# Z_-.net
KiCad netlist of a schematic drawn in EasyEDA Pro
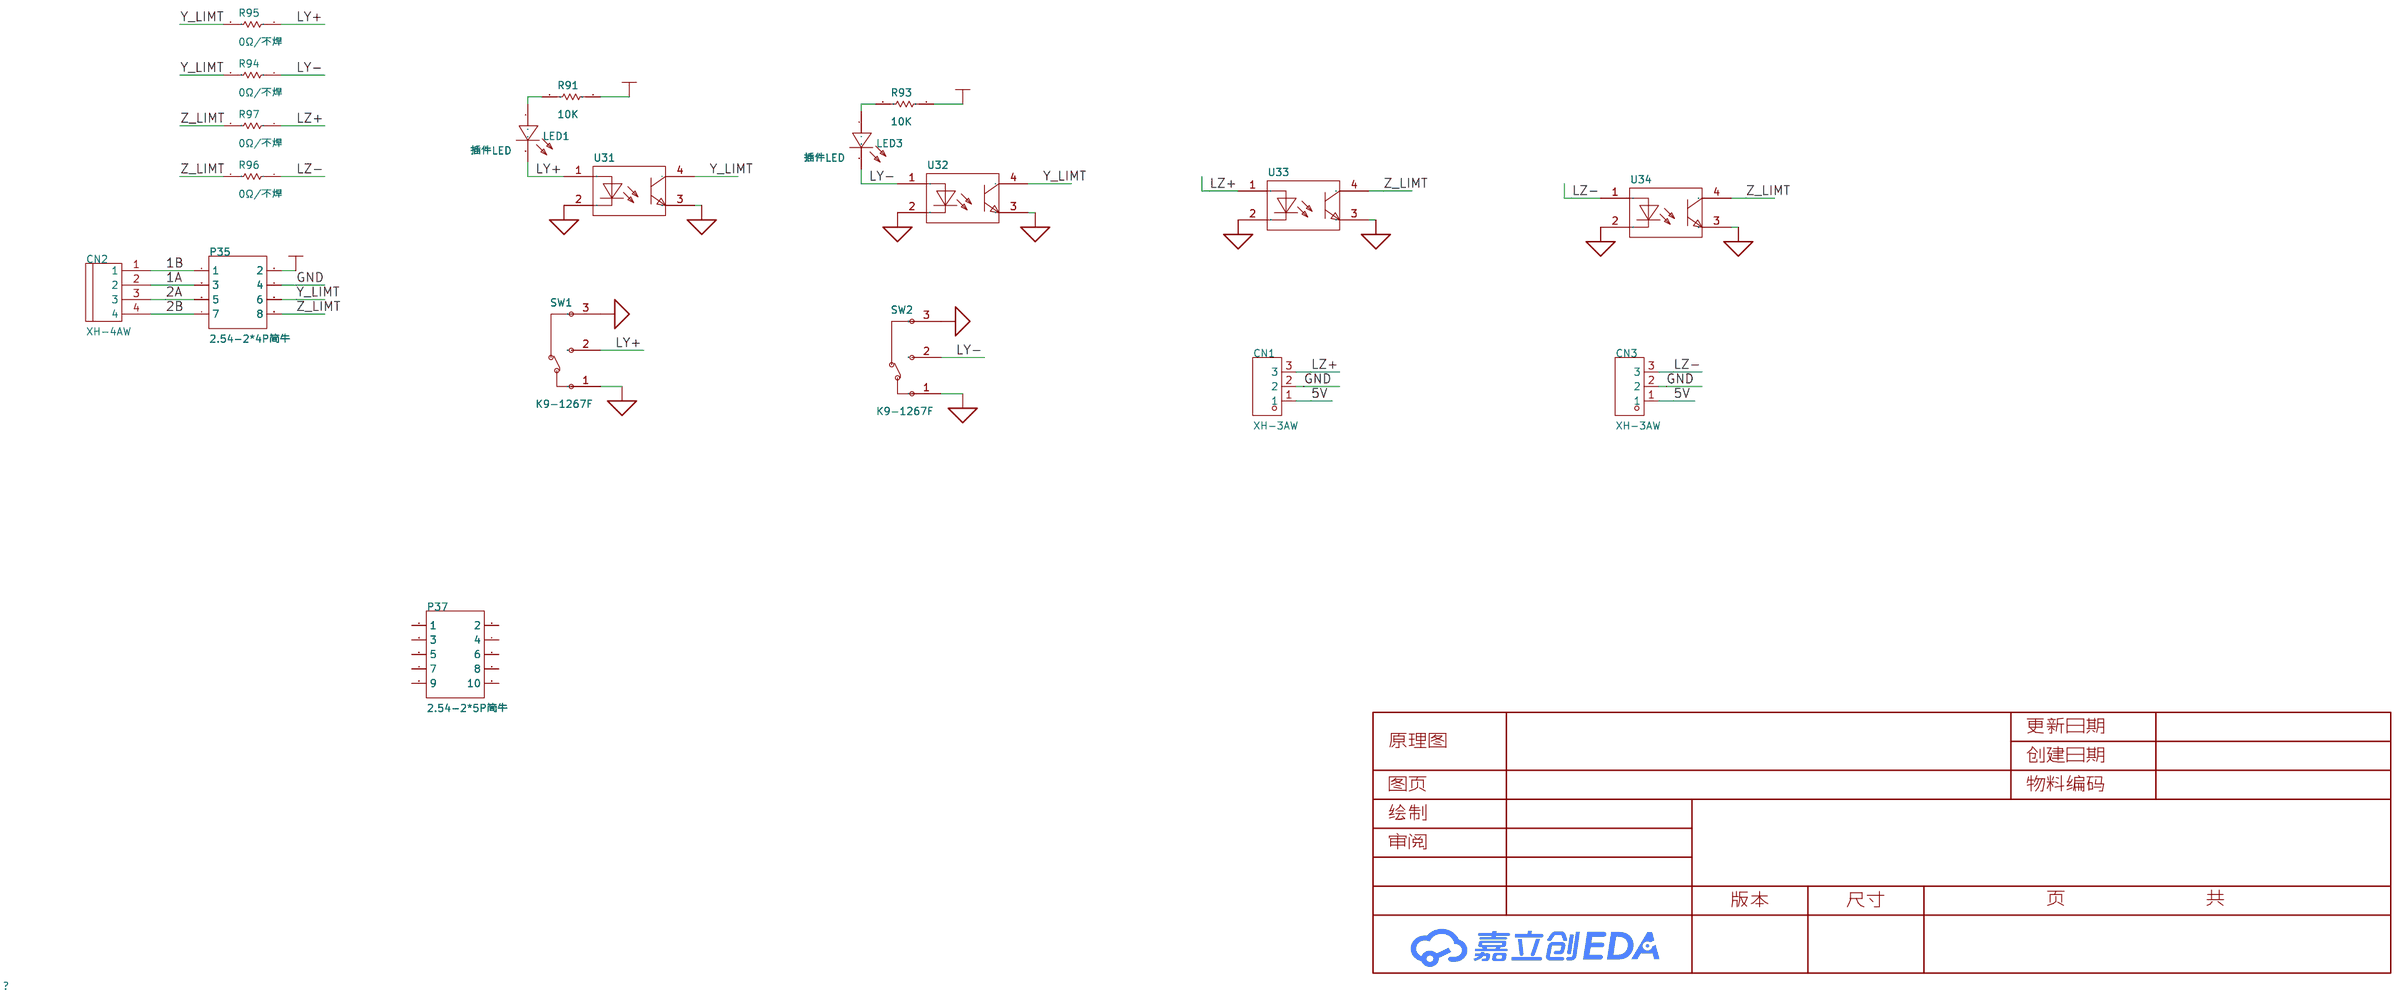
[diagram p0: 主控MCU]
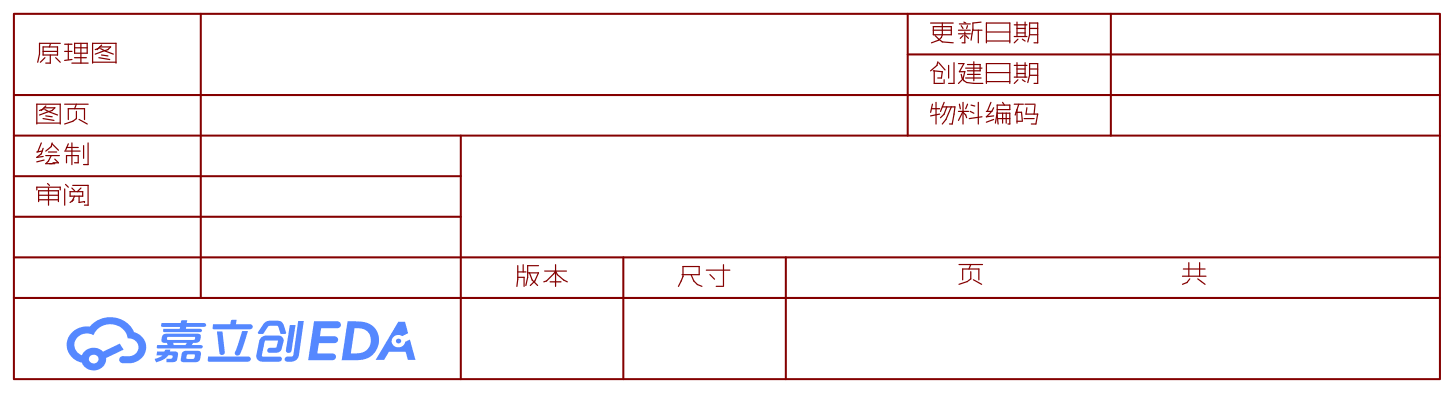
[diagram p1: 电源及控制]

(export (version "E")
  (design (tool "Eeschema 10.0.6"))
  (components
    (comp (ref "CN1")
      (value "XH-3AW")
      (footprint "easyedapro:CONN-TH_3P-P2.50_XH-3A")
      (description "参考系列:XH;间距:2.5mm;插针结构:1x3P;排数:1;每排PIN数:3;行距:-;安装方式:-;触头材质:-;")
      (fields (field (name "Manufacturer") "BOOMELE(博穆精密)"))
      (libsource (lib "easyedapro") (part "XH-3AW_C18428"))
    )
    (comp (ref "CN2")
      (value "XH-4AW")
      (footprint "easyedapro:CONN-TH_XH2.54-4AW")
      (description "参考系列:XH;间距:2.5mm;插针结构:1x4P;排数:1;每排PIN数:4;行距:-;安装方式:-;触头材质:磷青铜;")
      (fields (field (name "Manufacturer") "BOOMELE(博穆精密)"))
      (libsource (lib "easyedapro") (part "XH2.54-4AW"))
    )
    (comp (ref "CN3")
      (value "XH-3AW")
      (footprint "easyedapro:CONN-TH_3P-P2.50_XH-3A")
      (description "参考系列:XH;间距:2.5mm;插针结构:1x3P;排数:1;每排PIN数:3;行距:-;安装方式:-;触头材质:-;")
      (fields (field (name "Manufacturer") "BOOMELE(博穆精密)"))
      (libsource (lib "easyedapro") (part "XH-3AW_C18428"))
    )
    (comp (ref "LED1")
      (value "插件LED")
      (footprint "easyedapro:LED-TH_BD3.8-P2.54-FD")
      (description "发光颜色:红灯;")
      (fields (field (name "Manufacturer") "EVERLIGHT(台湾亿光)"))
      (libsource (lib "easyedapro") (part "204-10SURC/S530-A3-L"))
    )
    (comp (ref "LED3")
      (value "插件LED")
      (footprint "easyedapro:LED-TH_BD3.8-P2.54-FD")
      (description "发光颜色:红灯;")
      (fields (field (name "Manufacturer") "EVERLIGHT(台湾亿光)"))
      (libsource (lib "easyedapro") (part "204-10SURC/S530-A3-L"))
    )
    (comp (ref "P35")
      (value "2.54-2*4P简牛")
      (footprint "easyedapro:IDC-TH_8P-P2.54-V-R2-C4-S2.54")
      (description "连接器类型:简牛座;间距:2.54mm;每排PIN数:4;排数:2;行距:2.54mm;封装形式:直插;触头材质:-;触头镀层:-;")
      (fields (field (name "Manufacturer") "BOOMELE(博穆精密)"))
      (libsource (lib "easyedapro") (part "HDR-IDC-2.54-2X4P"))
    )
    (comp (ref "P37")
      (value "2.54-2*5P简牛")
      (footprint "easyedapro:IDC-TH_10P-P2.54_C5665")
      (description "连接器类型:简牛座;间距:2.54mm;每排PIN数:5;排数:2;行距:2.54mm;封装形式:直插;触头材质:-;触头镀层:-;")
      (fields (field (name "Manufacturer") "BOOMELE(博穆精密)"))
      (libsource (lib "easyedapro") (part "HDR-IDC-2.54-2X5P"))
    )
    (comp (ref "R91")
      (value "10K")
      (footprint "easyedapro:0603R")
      (description "Resistor")
      (libsource (lib "easyedapro") (part "RES"))
    )
    (comp (ref "R93")
      (value "10K")
      (footprint "easyedapro:0603R")
      (description "Resistor")
      (libsource (lib "easyedapro") (part "RES"))
    )
    (comp (ref "R94")
      (value "0Ω/不焊")
      (footprint "easyedapro:0603R")
      (description "Resistor")
      (libsource (lib "easyedapro") (part "RES"))
    )
    (comp (ref "R95")
      (value "0Ω/不焊")
      (footprint "easyedapro:0603R")
      (description "Resistor")
      (libsource (lib "easyedapro") (part "RES"))
    )
    (comp (ref "R96")
      (value "0Ω/不焊")
      (footprint "easyedapro:0603R")
      (description "Resistor")
      (libsource (lib "easyedapro") (part "RES"))
    )
    (comp (ref "R97")
      (value "0Ω/不焊")
      (footprint "easyedapro:0603R")
      (description "Resistor")
      (libsource (lib "easyedapro") (part "RES"))
    )
    (comp (ref "SW1")
      (value "K9-1267F")
      (footprint "easyedapro:SW-TH_K9-1267F")
      (fields (field (name "Manufacturer") "韩国韩荣"))
      (libsource (lib "easyedapro") (part "K9-1267F"))
    )
    (comp (ref "SW2")
      (value "K9-1267F")
      (footprint "easyedapro:SW-TH_K9-1267F")
      (fields (field (name "Manufacturer") "韩国韩荣"))
      (libsource (lib "easyedapro") (part "K9-1267F"))
    )
    (comp (ref "U31")
      (value "LTV-357T-C")
      (footprint "easyedapro:SOP-4_L4.4-W3.9-P2.54-LS7.0-TL")
      (fields (field (name "Manufacturer") "LITEON(光宝)"))
      (libsource (lib "easyedapro") (part "LTV-357T-C"))
    )
    (comp (ref "U32")
      (value "LTV-357T-C")
      (footprint "easyedapro:SOP-4_L4.4-W3.9-P2.54-LS7.0-TL")
      (fields (field (name "Manufacturer") "LITEON(光宝)"))
      (libsource (lib "easyedapro") (part "LTV-357T-C"))
    )
    (comp (ref "U33")
      (value "LTV-357T-C")
      (footprint "easyedapro:SOP-4_L4.4-W3.9-P2.54-LS7.0-TL")
      (fields (field (name "Manufacturer") "LITEON(光宝)"))
      (libsource (lib "easyedapro") (part "LTV-357T-C"))
    )
    (comp (ref "U34")
      (value "LTV-357T-C")
      (footprint "easyedapro:SOP-4_L4.4-W3.9-P2.54-LS7.0-TL")
      (fields (field (name "Manufacturer") "LITEON(光宝)"))
      (libsource (lib "easyedapro") (part "LTV-357T-C"))
    )
  )
  (nets
    (net (code "1") (name "1A") (class "Default")
      (node (ref "CN2") (pin "2") (pinfunction "2_2") (pintype "input"))
      (node (ref "P35") (pin "3") (pinfunction "3_3") (pintype "input"))
    )
    (net (code "2") (name "1B") (class "Default")
      (node (ref "CN2") (pin "1") (pinfunction "1_1") (pintype "input"))
      (node (ref "P35") (pin "1") (pinfunction "1_1") (pintype "input"))
    )
    (net (code "3") (name "2A") (class "Default")
      (node (ref "CN2") (pin "3") (pinfunction "3_3") (pintype "input"))
      (node (ref "P35") (pin "5") (pinfunction "5_5") (pintype "input"))
    )
    (net (code "4") (name "2B") (class "Default")
      (node (ref "CN2") (pin "4") (pinfunction "4_4") (pintype "input"))
      (node (ref "P35") (pin "7") (pinfunction "7_7") (pintype "input"))
    )
    (net (code "5") (name "5V") (class "Default")
      (node (ref "CN1") (pin "1") (pinfunction "1_1") (pintype "input"))
      (node (ref "CN3") (pin "1") (pinfunction "1_1") (pintype "input"))
      (node (ref "P35") (pin "2") (pinfunction "2_2") (pintype "input"))
      (node (ref "R91") (pin "1") (pinfunction "1_1") (pintype "unspecified"))
      (node (ref "R93") (pin "1") (pinfunction "1_1") (pintype "unspecified"))
    )
    (net (code "6") (name "GND") (class "Default")
      (node (ref "CN1") (pin "2") (pinfunction "2_2") (pintype "input"))
      (node (ref "CN3") (pin "2") (pinfunction "2_2") (pintype "input"))
      (node (ref "P35") (pin "4") (pinfunction "4_4") (pintype "input"))
      (node (ref "SW1") (pin "1") (pinfunction "C_1") (pintype "input"))
      (node (ref "SW1") (pin "3") (pinfunction "NC_3") (pintype "input"))
      (node (ref "SW2") (pin "1") (pinfunction "C_1") (pintype "input"))
      (node (ref "SW2") (pin "3") (pinfunction "NC_3") (pintype "input"))
      (node (ref "U31") (pin "2") (pinfunction "2_2") (pintype "unspecified"))
      (node (ref "U31") (pin "3") (pinfunction "3_3") (pintype "unspecified"))
      (node (ref "U32") (pin "2") (pinfunction "2_2") (pintype "unspecified"))
      (node (ref "U32") (pin "3") (pinfunction "3_3") (pintype "unspecified"))
      (node (ref "U33") (pin "2") (pinfunction "2_2") (pintype "unspecified"))
      (node (ref "U33") (pin "3") (pinfunction "3_3") (pintype "unspecified"))
      (node (ref "U34") (pin "2") (pinfunction "2_2") (pintype "unspecified"))
      (node (ref "U34") (pin "3") (pinfunction "3_3") (pintype "unspecified"))
    )
    (net (code "7") (name "LY+") (class "Default")
      (node (ref "LED1") (pin "2") (pinfunction "K_2") (pintype "input"))
      (node (ref "R95") (pin "1") (pinfunction "1_1") (pintype "unspecified"))
      (node (ref "SW1") (pin "2") (pinfunction "NO_2") (pintype "input"))
      (node (ref "U31") (pin "1") (pinfunction "1_1") (pintype "unspecified"))
    )
    (net (code "8") (name "LY-") (class "Default")
      (node (ref "LED3") (pin "2") (pinfunction "K_2") (pintype "input"))
      (node (ref "R94") (pin "1") (pinfunction "1_1") (pintype "unspecified"))
      (node (ref "SW2") (pin "2") (pinfunction "NO_2") (pintype "input"))
      (node (ref "U32") (pin "1") (pinfunction "1_1") (pintype "unspecified"))
    )
    (net (code "9") (name "LZ+") (class "Default")
      (node (ref "CN1") (pin "3") (pinfunction "3_3") (pintype "input"))
      (node (ref "R97") (pin "1") (pinfunction "1_1") (pintype "unspecified"))
      (node (ref "U33") (pin "1") (pinfunction "1_1") (pintype "unspecified"))
    )
    (net (code "10") (name "LZ-") (class "Default")
      (node (ref "CN3") (pin "3") (pinfunction "3_3") (pintype "input"))
      (node (ref "R96") (pin "1") (pinfunction "1_1") (pintype "unspecified"))
      (node (ref "U34") (pin "1") (pinfunction "1_1") (pintype "unspecified"))
    )
    (net (code "11") (name "Net-(LED1-A)") (class "Default")
      (node (ref "LED1") (pin "1") (pinfunction "A_1") (pintype "input"))
      (node (ref "R91") (pin "2") (pinfunction "2_2") (pintype "unspecified"))
    )
    (net (code "12") (name "Net-(LED3-A)") (class "Default")
      (node (ref "LED3") (pin "1") (pinfunction "A_1") (pintype "input"))
      (node (ref "R93") (pin "2") (pinfunction "2_2") (pintype "unspecified"))
    )
    (net (code "13") (name "Y_LIMT") (class "Default")
      (node (ref "P35") (pin "6") (pinfunction "6_6") (pintype "input"))
      (node (ref "R94") (pin "2") (pinfunction "2_2") (pintype "unspecified"))
      (node (ref "R95") (pin "2") (pinfunction "2_2") (pintype "unspecified"))
      (node (ref "U31") (pin "4") (pinfunction "4_4") (pintype "unspecified"))
      (node (ref "U32") (pin "4") (pinfunction "4_4") (pintype "unspecified"))
    )
    (net (code "14") (name "Z_LIMT") (class "Default")
      (node (ref "P35") (pin "8") (pinfunction "8_8") (pintype "input"))
      (node (ref "R96") (pin "2") (pinfunction "2_2") (pintype "unspecified"))
      (node (ref "R97") (pin "2") (pinfunction "2_2") (pintype "unspecified"))
      (node (ref "U33") (pin "4") (pinfunction "4_4") (pintype "unspecified"))
      (node (ref "U34") (pin "4") (pinfunction "4_4") (pintype "unspecified"))
    )
    (net (code "15") (name "unconnected-(P37-Pad1)") (class "Default")
      (node (ref "P37") (pin "1") (pinfunction "1_1") (pintype "input"))
    )
    (net (code "16") (name "unconnected-(P37-Pad2)") (class "Default")
      (node (ref "P37") (pin "2") (pinfunction "2_2") (pintype "input"))
    )
    (net (code "17") (name "unconnected-(P37-Pad3)") (class "Default")
      (node (ref "P37") (pin "3") (pinfunction "3_3") (pintype "input"))
    )
    (net (code "18") (name "unconnected-(P37-Pad4)") (class "Default")
      (node (ref "P37") (pin "4") (pinfunction "4_4") (pintype "input"))
    )
    (net (code "19") (name "unconnected-(P37-Pad5)") (class "Default")
      (node (ref "P37") (pin "5") (pinfunction "5_5") (pintype "input"))
    )
    (net (code "20") (name "unconnected-(P37-Pad6)") (class "Default")
      (node (ref "P37") (pin "6") (pinfunction "6_6") (pintype "input"))
    )
    (net (code "21") (name "unconnected-(P37-Pad7)") (class "Default")
      (node (ref "P37") (pin "7") (pinfunction "7_7") (pintype "input"))
    )
    (net (code "22") (name "unconnected-(P37-Pad8)") (class "Default")
      (node (ref "P37") (pin "8") (pinfunction "8_8") (pintype "input"))
    )
    (net (code "23") (name "unconnected-(P37-Pad9)") (class "Default")
      (node (ref "P37") (pin "9") (pinfunction "9_9") (pintype "input"))
    )
    (net (code "24") (name "unconnected-(P37-Pad10)") (class "Default")
      (node (ref "P37") (pin "10") (pinfunction "10_10") (pintype "input"))
    )
  )
)
